# fet.net
KiCad netlist of a schematic drawn in Altium Designer
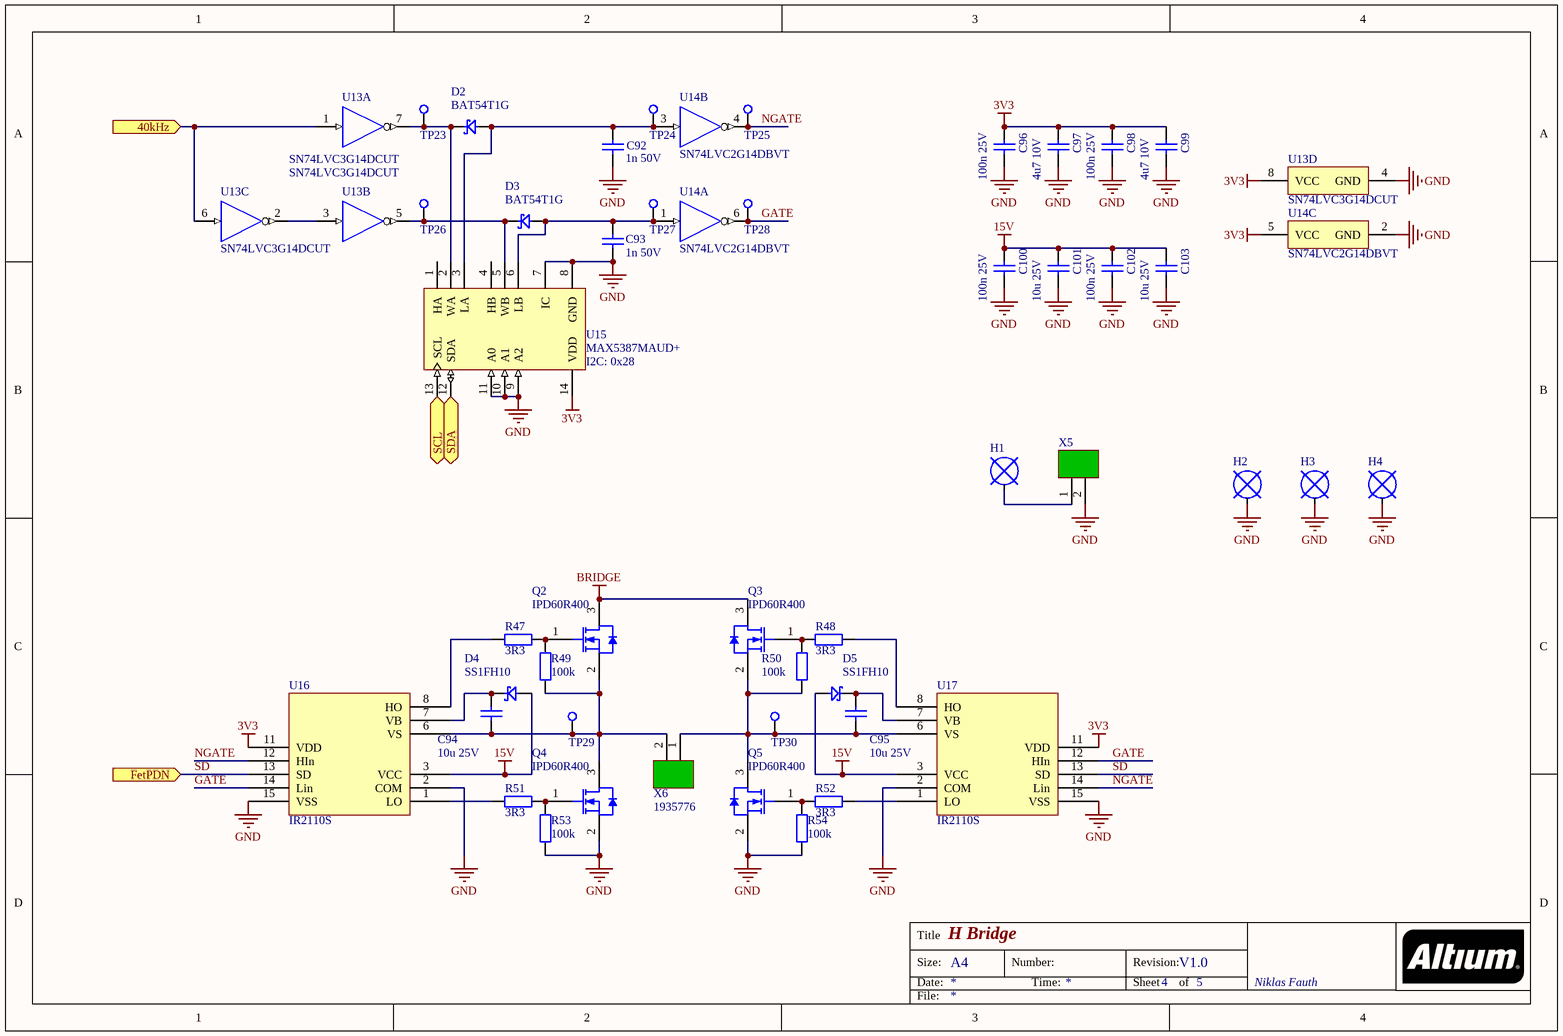
[diagram p0: fet.SchDoc]

(export (version "E")
  (design (tool "Eeschema 10.0.6"))
  (components
    (comp (ref "C92")
      (value "1n 50V")
      (footprint "C-0603-H")
      (description "Capacitor 1nF 50V")
      (libsource (lib "Passives") (part "C-0603-1n-50V"))
    )
    (comp (ref "C93")
      (value "1n 50V")
      (footprint "C-0603-H")
      (description "Capacitor 1nF 50V")
      (libsource (lib "Passives") (part "C-0603-1n-50V"))
    )
    (comp (ref "C94")
      (value "10u 25V")
      (footprint "C-0805-H")
      (description "Capacitor 10u 25V")
      (libsource (lib "Passives") (part "C-0805-10u-25V"))
    )
    (comp (ref "C95")
      (value "10u 25V")
      (footprint "C-0805-H")
      (description "Capacitor 10u 25V")
      (libsource (lib "Passives") (part "C-0805-10u-25V"))
    )
    (comp (ref "C96")
      (value "100n 25V")
      (footprint "C-0603-H")
      (description "Capacitor 100n 25V")
      (libsource (lib "Passives") (part "C-0603-100n-25V"))
    )
    (comp (ref "C97")
      (value "4u7 10V")
      (footprint "C-0603-H")
      (description "Capacitor 4.7uF 10V")
      (libsource (lib "Passives") (part "C-0603-4u7-10V"))
    )
    (comp (ref "C98")
      (value "100n 25V")
      (footprint "C-0603-H")
      (description "Capacitor 100n 25V")
      (libsource (lib "Passives") (part "C-0603-100n-25V"))
    )
    (comp (ref "C99")
      (value "4u7 10V")
      (footprint "C-0603-H")
      (description "Capacitor 4.7uF 10V")
      (libsource (lib "Passives") (part "C-0603-4u7-10V"))
    )
    (comp (ref "C100")
      (value "100n 25V")
      (footprint "C-0603-H")
      (description "Capacitor 100n 25V")
      (libsource (lib "Passives") (part "C-0603-100n-25V"))
    )
    (comp (ref "C101")
      (value "10u 25V")
      (footprint "C-0805-H")
      (description "Capacitor 10u 25V")
      (libsource (lib "Passives") (part "C-0805-10u-25V"))
    )
    (comp (ref "C102")
      (value "100n 25V")
      (footprint "C-0603-H")
      (description "Capacitor 100n 25V")
      (libsource (lib "Passives") (part "C-0603-100n-25V"))
    )
    (comp (ref "C103")
      (value "10u 25V")
      (footprint "C-0805-H")
      (description "Capacitor 10u 25V")
      (libsource (lib "Passives") (part "C-0805-10u-25V"))
    )
    (comp (ref "D2") (value "BAT54T1G") (footprint "SOD123") (libsource (lib "advanced") (part "D-BAT54T1G")))
    (comp (ref "D3") (value "BAT54T1G") (footprint "SOD123") (libsource (lib "advanced") (part "D-BAT54T1G")))
    (comp (ref "D4")
      (value "SS1FH10")
      (footprint "DO-219AB (SMF)")
      (libsource (lib "advanced") (part "D-SS1FH10"))
    )
    (comp (ref "D5")
      (value "SS1FH10")
      (footprint "DO-219AB (SMF)")
      (libsource (lib "advanced") (part "D-SS1FH10"))
    )
    (comp (ref "H1")
      (value "WE-ST-5MM-F")
      (footprint "WE-Standoff-5MM-M3-Female")
      (description "WE-Standoff-M3-5MM-Female")
      (libsource (lib "advanced") (part "WE-Standoff-M3-5MM-Female"))
    )
    (comp (ref "H2")
      (value "WE-ST-5MM-F")
      (footprint "WE-Standoff-5MM-M3-Female")
      (description "WE-Standoff-M3-5MM-Female")
      (libsource (lib "advanced") (part "WE-Standoff-M3-5MM-Female"))
    )
    (comp (ref "H3")
      (value "WE-ST-5MM-F")
      (footprint "WE-Standoff-5MM-M3-Female")
      (description "WE-Standoff-M3-5MM-Female")
      (libsource (lib "advanced") (part "WE-Standoff-M3-5MM-Female"))
    )
    (comp (ref "H4")
      (value "WE-ST-5MM-F")
      (footprint "WE-Standoff-5MM-M3-Female")
      (description "WE-Standoff-M3-5MM-Female")
      (libsource (lib "advanced") (part "WE-Standoff-M3-5MM-Female"))
    )
    (comp (ref "Q2")
      (value "IPD60R400")
      (footprint "TO-252")
      (libsource (lib "advanced") (part "MOSFET-IPD60R400"))
    )
    (comp (ref "Q3")
      (value "IPD60R400")
      (footprint "TO-252")
      (libsource (lib "advanced") (part "MOSFET-IPD60R400"))
    )
    (comp (ref "Q4")
      (value "IPD60R400")
      (footprint "TO-252")
      (libsource (lib "advanced") (part "MOSFET-IPD60R400"))
    )
    (comp (ref "Q5")
      (value "IPD60R400")
      (footprint "TO-252")
      (libsource (lib "advanced") (part "MOSFET-IPD60R400"))
    )
    (comp (ref "R47")
      (value "3R3")
      (footprint "R-0603-H")
      (description "Resistor 3R3")
      (libsource (lib "Passives") (part "R-0603-3R3"))
    )
    (comp (ref "R48")
      (value "3R3")
      (footprint "R-0603-H")
      (description "Resistor 3R3")
      (libsource (lib "") (part "R-0603-3R3_1"))
    )
    (comp (ref "R49")
      (value "100k")
      (footprint "R-0603-M")
      (description "Resistor 100k")
      (libsource (lib "Passives") (part "R-0603-100k"))
    )
    (comp (ref "R50")
      (value "100k")
      (footprint "R-0603-M")
      (description "Resistor 100k")
      (libsource (lib "Passives") (part "R-0603-100k"))
    )
    (comp (ref "R51")
      (value "3R3")
      (footprint "R-0603-H")
      (description "Resistor 3R3")
      (libsource (lib "Passives") (part "R-0603-3R3"))
    )
    (comp (ref "R52")
      (value "3R3")
      (footprint "R-0603-H")
      (description "Resistor 3R3")
      (libsource (lib "") (part "R-0603-3R3_1"))
    )
    (comp (ref "R53")
      (value "100k")
      (footprint "R-0603-M")
      (description "Resistor 100k")
      (libsource (lib "Passives") (part "R-0603-100k"))
    )
    (comp (ref "R54")
      (value "100k")
      (footprint "R-0603-M")
      (description "Resistor 100k")
      (libsource (lib "Passives") (part "R-0603-100k"))
    )
    (comp (ref "TP23") (value "TP-SMD") (footprint "TP") (libsource (lib "advanced") (part "TP-SMD")))
    (comp (ref "TP24") (value "TP-SMD") (footprint "TP") (libsource (lib "advanced") (part "TP-SMD")))
    (comp (ref "TP25") (value "TP-SMD") (footprint "TP") (libsource (lib "advanced") (part "TP-SMD")))
    (comp (ref "TP26") (value "TP-SMD") (footprint "TP") (libsource (lib "advanced") (part "TP-SMD")))
    (comp (ref "TP27") (value "TP-SMD") (footprint "TP") (libsource (lib "advanced") (part "TP-SMD")))
    (comp (ref "TP28") (value "TP-SMD") (footprint "TP") (libsource (lib "advanced") (part "TP-SMD")))
    (comp (ref "TP29") (value "TP-SMD") (footprint "TP") (libsource (lib "advanced") (part "TP-SMD")))
    (comp (ref "TP30") (value "TP-SMD") (footprint "TP") (libsource (lib "advanced") (part "TP-SMD")))
    (comp (ref "U13")
      (value "SN74LVC3G14DCUT")
      (footprint "DCU0008A_N")
      (description "Triple Schmitt-Trigger Inverter, DCU0008A, SMALL T&R")
      (fields
        (field (name "MANUFACTURER") "Texas Instruments")
        (field (name "GENERIC PART NUMBER") "SN74LVC3G14")
      )
      (libsource (lib "Altium Content Vault") (part "TI-SN74XXX3GXX-8"))
    )
    (comp (ref "U14")
      (value "SN74LVC2G14DBVT")
      (footprint "DBV0006A_N")
      (description "Dual Schmitt-Trigger Inverter, DBV0006A, SMALL T&R")
      (fields
        (field (name "GENERIC PART NUMBER") "SN74LVC2G14")
        (field (name "MANUFACTURER") "Texas Instruments")
      )
      (libsource (lib "Altium Content Vault") (part "TI-SN74XXX2GXXX-6"))
    )
    (comp (ref "U15")
      (value "MAX5387MAUD+")
      (footprint "MAXM-U14+1_N")
      (libsource (lib "Altium Content Vault") (part "MAX5387-U14+1"))
    )
    (comp (ref "U16")
      (value "IR2110S")
      (footprint "SOIC127P1030X265-16N")
      (libsource (lib "advanced") (part "IR2110S"))
    )
    (comp (ref "U17")
      (value "IR2110S")
      (footprint "SOIC127P1030X265-16N")
      (libsource (lib "") (part "IR2110S_1"))
    )
    (comp (ref "X5")
      (value "1935776")
      (footprint "PHOENIX-2P-5mm")
      (libsource (lib "") (part "PHOENIX-2P-5MM_1"))
    )
    (comp (ref "X6")
      (value "1935776")
      (footprint "PHOENIX-2P-5mm")
      (libsource (lib "advanced") (part "PHOENIX-2P-5MM"))
    )
  )
  (nets
    (net (code "1") (name "/40kHz") (class "Default")
      (node (ref "U13") (pin "1") (pinfunction "1A_1") (pintype "input"))
      (node (ref "U13") (pin "6") (pinfunction "3A_6") (pintype "input"))
    )
    (net (code "2") (name "/GATE") (class "Default")
      (node (ref "TP28") (pin "1") (pintype "passive"))
      (node (ref "U14") (pin "6") (pinfunction "1Y_6") (pintype "output"))
      (node (ref "U16") (pin "14") (pinfunction "Lin_14") (pintype "passive"))
      (node (ref "U17") (pin "12") (pinfunction "HIn_12") (pintype "passive"))
    )
    (net (code "3") (name "/NGATE") (class "Default")
      (node (ref "TP25") (pin "1") (pintype "passive"))
      (node (ref "U14") (pin "4") (pinfunction "2Y_4") (pintype "output"))
      (node (ref "U16") (pin "12") (pinfunction "HIn_12") (pintype "passive"))
      (node (ref "U17") (pin "14") (pinfunction "Lin_14") (pintype "passive"))
    )
    (net (code "4") (name "/SCL") (class "Default")
      (node (ref "U15") (pin "13") (pinfunction "SCL_13") (pintype "input"))
    )
    (net (code "5") (name "/SD") (class "Default")
      (node (ref "U16") (pin "13") (pinfunction "SD_13") (pintype "passive"))
      (node (ref "U17") (pin "13") (pinfunction "SD_13") (pintype "passive"))
    )
    (net (code "6") (name "/SDA") (class "Default")
      (node (ref "U15") (pin "12") (pinfunction "SDA_12") (pintype "bidirectional"))
    )
    (net (code "7") (name "3V3") (class "Default")
      (node (ref "C96") (pin "2") (pinfunction "2_2") (pintype "passive"))
      (node (ref "C97") (pin "2") (pinfunction "2_2") (pintype "passive"))
      (node (ref "C98") (pin "2") (pinfunction "2_2") (pintype "passive"))
      (node (ref "C99") (pin "2") (pinfunction "2_2") (pintype "passive"))
      (node (ref "U13") (pin "8") (pinfunction "VCC_8") (pintype "power_in"))
      (node (ref "U14") (pin "5") (pinfunction "VCC_5") (pintype "power_in"))
      (node (ref "U15") (pin "14") (pinfunction "VDD_14") (pintype "power_in"))
      (node (ref "U16") (pin "11") (pinfunction "VDD_11") (pintype "passive"))
      (node (ref "U17") (pin "11") (pinfunction "VDD_11") (pintype "passive"))
    )
    (net (code "8") (name "15V") (class "Default")
      (node (ref "C100") (pin "2") (pinfunction "2_2") (pintype "passive"))
      (node (ref "C101") (pin "2") (pinfunction "2_2") (pintype "passive"))
      (node (ref "C102") (pin "2") (pinfunction "2_2") (pintype "passive"))
      (node (ref "C103") (pin "2") (pinfunction "2_2") (pintype "passive"))
      (node (ref "D4") (pin "1") (pinfunction "an_1") (pintype "passive"))
      (node (ref "D5") (pin "1") (pinfunction "an_1") (pintype "passive"))
      (node (ref "U16") (pin "3") (pinfunction "VCC_3") (pintype "passive"))
      (node (ref "U17") (pin "3") (pinfunction "VCC_3") (pintype "passive"))
    )
    (net (code "9") (name "BRIDGE") (class "Default")
      (node (ref "Q2") (pin "3") (pintype "passive"))
      (node (ref "Q3") (pin "3") (pintype "passive"))
    )
    (net (code "10") (name "GND") (class "Default")
      (node (ref "C100") (pin "1") (pinfunction "1_1") (pintype "passive"))
      (node (ref "C101") (pin "1") (pinfunction "1_1") (pintype "passive"))
      (node (ref "C102") (pin "1") (pinfunction "1_1") (pintype "passive"))
      (node (ref "C103") (pin "1") (pinfunction "1_1") (pintype "passive"))
      (node (ref "C92") (pin "1") (pinfunction "1_1") (pintype "passive"))
      (node (ref "C93") (pin "1") (pinfunction "1_1") (pintype "passive"))
      (node (ref "C96") (pin "1") (pinfunction "1_1") (pintype "passive"))
      (node (ref "C97") (pin "1") (pinfunction "1_1") (pintype "passive"))
      (node (ref "C98") (pin "1") (pinfunction "1_1") (pintype "passive"))
      (node (ref "C99") (pin "1") (pinfunction "1_1") (pintype "passive"))
      (node (ref "H2") (pin "0") (pinfunction "GND_0") (pintype "power_in"))
      (node (ref "H3") (pin "0") (pinfunction "GND_0") (pintype "power_in"))
      (node (ref "H4") (pin "0") (pinfunction "GND_0") (pintype "power_in"))
      (node (ref "Q4") (pin "2") (pintype "passive"))
      (node (ref "Q5") (pin "2") (pintype "passive"))
      (node (ref "R53") (pin "1") (pinfunction "1_1") (pintype "passive"))
      (node (ref "R54") (pin "1") (pinfunction "1_1") (pintype "passive"))
      (node (ref "U13") (pin "4") (pinfunction "GND_4") (pintype "power_in"))
      (node (ref "U14") (pin "2") (pinfunction "GND_2") (pintype "power_in"))
      (node (ref "U15") (pin "10") (pinfunction "A1_10") (pintype "input"))
      (node (ref "U15") (pin "11") (pinfunction "A0_11") (pintype "input"))
      (node (ref "U15") (pin "7") (pinfunction "IC_7") (pintype "passive"))
      (node (ref "U15") (pin "8") (pinfunction "GND_8") (pintype "power_in"))
      (node (ref "U15") (pin "9") (pinfunction "A2_9") (pintype "input"))
      (node (ref "U16") (pin "15") (pinfunction "VSS_15") (pintype "passive"))
      (node (ref "U16") (pin "2") (pinfunction "COM_2") (pintype "passive"))
      (node (ref "U17") (pin "15") (pinfunction "VSS_15") (pintype "passive"))
      (node (ref "U17") (pin "2") (pinfunction "COM_2") (pintype "passive"))
      (node (ref "X5") (pin "2") (pinfunction "GND_2") (pintype "passive"))
    )
    (net (code "11") (name "Net-(D2-an)") (class "Default")
      (node (ref "C92") (pin "2") (pinfunction "2_2") (pintype "passive"))
      (node (ref "D2") (pin "1") (pinfunction "an_1") (pintype "passive"))
      (node (ref "TP24") (pin "1") (pintype "passive"))
      (node (ref "U14") (pin "3") (pinfunction "2A_3") (pintype "input"))
      (node (ref "U15") (pin "3") (pinfunction "LA_3") (pintype "passive"))
    )
    (net (code "12") (name "Net-(D2-kt)") (class "Default")
      (node (ref "D2") (pin "2") (pinfunction "kt_2") (pintype "passive"))
      (node (ref "TP23") (pin "1") (pintype "passive"))
      (node (ref "U13") (pin "7") (pinfunction "1Y_7") (pintype "output"))
      (node (ref "U15") (pin "2") (pinfunction "WA_2") (pintype "passive"))
    )
    (net (code "13") (name "Net-(D3-an)") (class "Default")
      (node (ref "C93") (pin "2") (pinfunction "2_2") (pintype "passive"))
      (node (ref "D3") (pin "1") (pinfunction "an_1") (pintype "passive"))
      (node (ref "TP27") (pin "1") (pintype "passive"))
      (node (ref "U14") (pin "1") (pinfunction "1A_1") (pintype "input"))
      (node (ref "U15") (pin "6") (pinfunction "LB_6") (pintype "passive"))
    )
    (net (code "14") (name "Net-(D3-kt)") (class "Default")
      (node (ref "D3") (pin "2") (pinfunction "kt_2") (pintype "passive"))
      (node (ref "TP26") (pin "1") (pintype "passive"))
      (node (ref "U13") (pin "5") (pinfunction "2Y_5") (pintype "output"))
      (node (ref "U15") (pin "5") (pinfunction "WB_5") (pintype "passive"))
    )
    (net (code "15") (name "Net-(D4-kt)") (class "Default")
      (node (ref "C94") (pin "2") (pinfunction "2_2") (pintype "passive"))
      (node (ref "D4") (pin "2") (pinfunction "kt_2") (pintype "passive"))
      (node (ref "U16") (pin "7") (pinfunction "VB_7") (pintype "passive"))
    )
    (net (code "16") (name "Net-(D5-kt)") (class "Default")
      (node (ref "C95") (pin "2") (pinfunction "2_2") (pintype "passive"))
      (node (ref "D5") (pin "2") (pinfunction "kt_2") (pintype "passive"))
      (node (ref "U17") (pin "7") (pinfunction "VB_7") (pintype "passive"))
    )
    (net (code "17") (name "Net-(H1-GND)") (class "Default")
      (node (ref "H1") (pin "0") (pinfunction "GND_0") (pintype "power_in"))
      (node (ref "X5") (pin "1") (pinfunction "GND_1") (pintype "passive"))
    )
    (net (code "18") (name "Net-(Q2-Pad1)") (class "Default")
      (node (ref "Q2") (pin "1") (pintype "passive"))
      (node (ref "R47") (pin "2") (pinfunction "2_2") (pintype "passive"))
      (node (ref "R49") (pin "2") (pinfunction "2_2") (pintype "passive"))
    )
    (net (code "19") (name "Net-(Q3-Pad1)") (class "Default")
      (node (ref "Q3") (pin "1") (pintype "passive"))
      (node (ref "R48") (pin "2") (pinfunction "2_2") (pintype "passive"))
      (node (ref "R50") (pin "2") (pinfunction "2_2") (pintype "passive"))
    )
    (net (code "20") (name "Net-(Q4-Pad1)") (class "Default")
      (node (ref "Q4") (pin "1") (pintype "passive"))
      (node (ref "R51") (pin "2") (pinfunction "2_2") (pintype "passive"))
      (node (ref "R53") (pin "2") (pinfunction "2_2") (pintype "passive"))
    )
    (net (code "21") (name "Net-(Q5-Pad1)") (class "Default")
      (node (ref "Q5") (pin "1") (pintype "passive"))
      (node (ref "R52") (pin "2") (pinfunction "2_2") (pintype "passive"))
      (node (ref "R54") (pin "2") (pinfunction "2_2") (pintype "passive"))
    )
    (net (code "22") (name "Net-(U13B-2A)") (class "Default")
      (node (ref "U13") (pin "2") (pinfunction "3Y_2") (pintype "output"))
      (node (ref "U13") (pin "3") (pinfunction "2A_3") (pintype "input"))
    )
    (net (code "23") (name "Net-(U16-HO)") (class "Default")
      (node (ref "R47") (pin "1") (pinfunction "1_1") (pintype "passive"))
      (node (ref "U16") (pin "8") (pinfunction "HO_8") (pintype "passive"))
    )
    (net (code "24") (name "Net-(U16-LO)") (class "Default")
      (node (ref "R51") (pin "1") (pinfunction "1_1") (pintype "passive"))
      (node (ref "U16") (pin "1") (pinfunction "LO_1") (pintype "passive"))
    )
    (net (code "25") (name "Net-(U16-VS)") (class "Default")
      (node (ref "C94") (pin "1") (pinfunction "1_1") (pintype "passive"))
      (node (ref "Q2") (pin "2") (pintype "passive"))
      (node (ref "Q4") (pin "3") (pintype "passive"))
      (node (ref "R49") (pin "1") (pinfunction "1_1") (pintype "passive"))
      (node (ref "TP29") (pin "1") (pintype "passive"))
      (node (ref "U16") (pin "6") (pinfunction "VS_6") (pintype "passive"))
      (node (ref "X6") (pin "2") (pinfunction "GND_2") (pintype "passive"))
    )
    (net (code "26") (name "Net-(U17-HO)") (class "Default")
      (node (ref "R48") (pin "1") (pinfunction "1_1") (pintype "passive"))
      (node (ref "U17") (pin "8") (pinfunction "HO_8") (pintype "passive"))
    )
    (net (code "27") (name "Net-(U17-LO)") (class "Default")
      (node (ref "R52") (pin "1") (pinfunction "1_1") (pintype "passive"))
      (node (ref "U17") (pin "1") (pinfunction "LO_1") (pintype "passive"))
    )
    (net (code "28") (name "Net-(U17-VS)") (class "Default")
      (node (ref "C95") (pin "1") (pinfunction "1_1") (pintype "passive"))
      (node (ref "Q3") (pin "2") (pintype "passive"))
      (node (ref "Q5") (pin "3") (pintype "passive"))
      (node (ref "R50") (pin "1") (pinfunction "1_1") (pintype "passive"))
      (node (ref "TP30") (pin "1") (pintype "passive"))
      (node (ref "U17") (pin "6") (pinfunction "VS_6") (pintype "passive"))
      (node (ref "X6") (pin "1") (pinfunction "GND_1") (pintype "passive"))
    )
    (net (code "29") (name "unconnected-(U15-HA-Pad1)") (class "Default")
      (node (ref "U15") (pin "1") (pinfunction "HA_1") (pintype "passive"))
    )
    (net (code "30") (name "unconnected-(U15-HB-Pad4)") (class "Default")
      (node (ref "U15") (pin "4") (pinfunction "HB_4") (pintype "passive"))
    )
  )
)
